# 20-Power-P1V8.net
KiCad netlist of a schematic drawn in Altium Designer
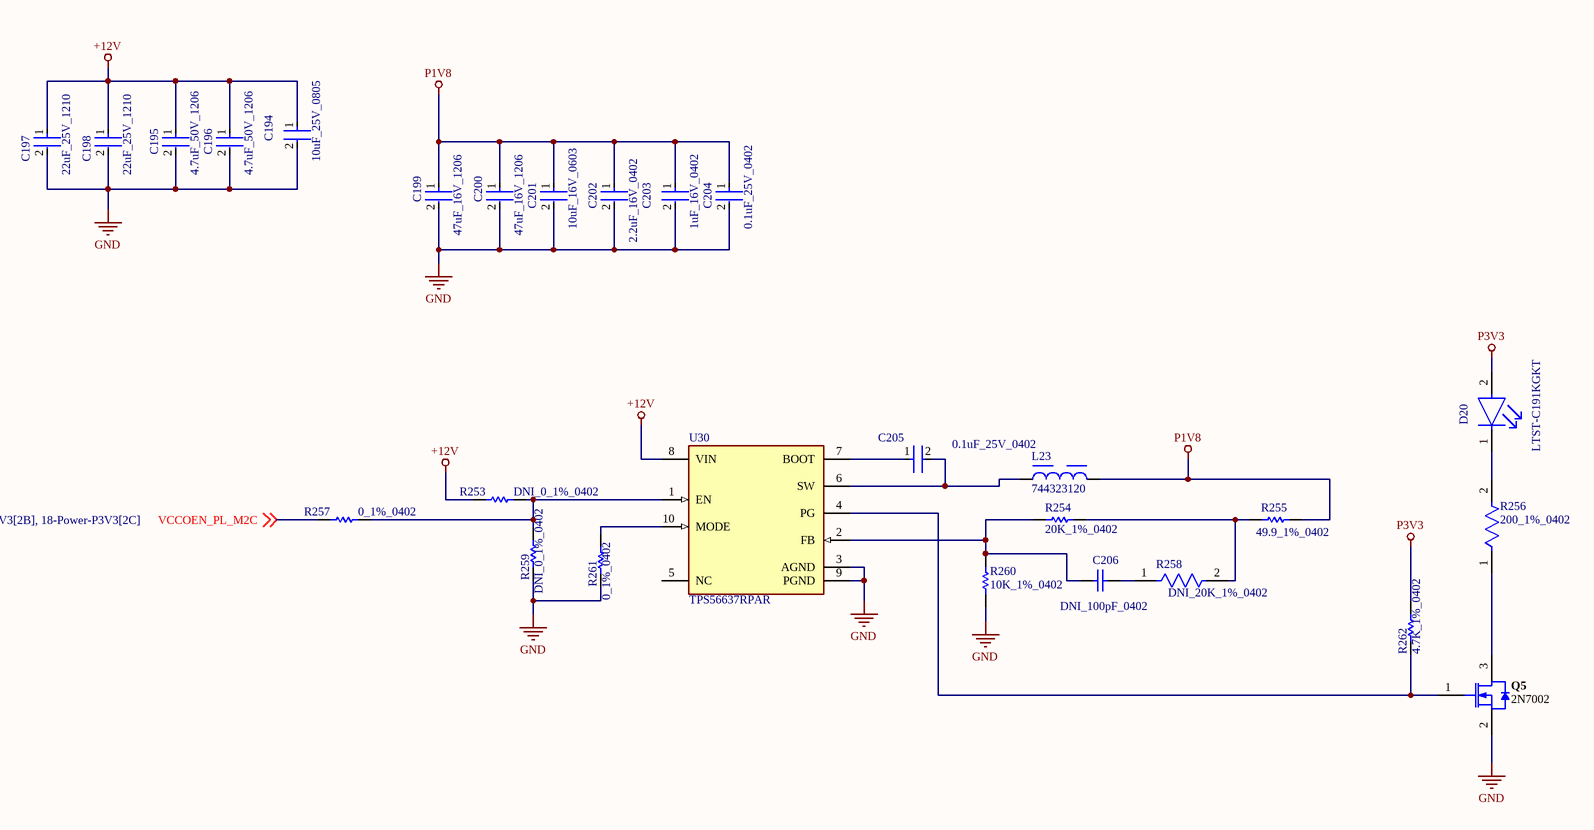
[diagram p0: 20-Power-P1V8.SchDoc]

(export (version "E")
  (design (tool "Eeschema 10.0.6"))
  (components
    (comp (ref "C194")
      (value "10uF_25V_0805")
      (footprint "FP-0805-L_2_0_0_2-W_1_25-MFG")
      (description "Multilayer Ceramic Capacitor 10uF 25V X5R 10% SMD 0805 T/R")
      (fields (field (name "VOLTAGE") "16V") (field (name "TOLERANCE") "10%"))
      (libsource (lib "Altium Content Vault") (part "02cd4be3c70576c341d710602a673aa"))
    )
    (comp (ref "C195")
      (value "4.7uF_50V_1206")
      (footprint "FP-GRM31C-0_2-e0_3_0_8-IPC_C")
      (description "Chip Multilayer Ceramic Capacitors for General Purpose, 1206, 4.7uF, X7R, 15%, 10%, 50V")
      (fields (field (name "VOLTAGE") "50V") (field (name "TOLERANCE") "10%"))
      (libsource (lib "Altium Content Vault") (part "02cd4be3c70576c341d710602a673aa"))
    )
    (comp (ref "C196")
      (value "4.7uF_50V_1206")
      (footprint "FP-GRM31C-0_2-e0_3_0_8-IPC_C")
      (description "Chip Multilayer Ceramic Capacitors for General Purpose, 1206, 4.7uF, X7R, 15%, 10%, 50V")
      (fields (field (name "VOLTAGE") "50V") (field (name "TOLERANCE") "10%"))
      (libsource (lib "Altium Content Vault") (part "02cd4be3c70576c341d710602a673aa"))
    )
    (comp (ref "C197")
      (value "22uF_25V_1210")
      (footprint "FP-MK325M-MFG")
      (description "CAP CER 22UF 25V X5R 1210")
      (fields (field (name "TOLERANCE") "20%"))
      (libsource (lib "Altium Content Vault") (part "b4654b650e69147ec39a6b967a45e02"))
    )
    (comp (ref "C198")
      (value "22uF_25V_1210")
      (footprint "FP-MK325M-MFG")
      (description "CAP CER 22UF 25V X5R 1210")
      (fields (field (name "TOLERANCE") "20%"))
      (libsource (lib "Altium Content Vault") (part "b4654b650e69147ec39a6b967a45e02"))
    )
    (comp (ref "C199")
      (value "47uF_16V_1206")
      (footprint "FP-C3216-160-0_2-MFG")
      (description "Multilayer Ceramic Capacitors 47uF ±20% 16V X5R SMD 1206")
      (fields (field (name "TOLERANCE") "20%"))
      (libsource (lib "Altium Content Vault") (part "11868f565c42a9108669ba33697ecf6"))
    )
    (comp (ref "C200")
      (value "47uF_16V_1206")
      (footprint "FP-C3216-160-0_2-MFG")
      (description "Multilayer Ceramic Capacitors 47uF ±20% 16V X5R SMD 1206")
      (fields (field (name "TOLERANCE") "20%"))
      (libsource (lib "Altium Content Vault") (part "11868f565c42a9108669ba33697ecf6"))
    )
    (comp (ref "C201")
      (value "10uF_16V_0603")
      (footprint "FP-0603-L_1_6_0_2-W_0_8_0-MFG")
      (description "Multilayer Ceramic Capacitor 10uF 16V X5R 20% SMD 0603 T/R")
      (fields (field (name "TOLERANCE") "20%"))
      (libsource (lib "Altium Content Vault") (part "b4654b650e69147ec39a6b967a45e02"))
    )
    (comp (ref "C202")
      (value "2.2uF_16V_0402")
      (footprint "FP-C1005-050-0_05-IPC_A")
      (description "Multilayer Ceramic Capacitors 2.2μF ±10% 16V X5R SMD 0402")
      (fields (field (name "TOLERANCE") "10%"))
      (libsource (lib "Altium Content Vault") (part "b4654b650e69147ec39a6b967a45e02"))
    )
    (comp (ref "C203")
      (value "1uF_16V_0402")
      (footprint "FP-0402-L_1_0_0_05-W_0_5-IPC_A")
      (description "None")
      (fields (field (name "TOLERANCE") "10%"))
      (libsource (lib "Altium Content Vault") (part "b4654b650e69147ec39a6b967a45e02"))
    )
    (comp (ref "C204")
      (value "0.1uF_25V_0402")
      (footprint "FP-0402-L_1_0_1-W_0_5_0_1-IPC_C")
      (description "General Purpose Ceramic Capacitor, 0402, 100nF, 10%, X7R, 15%, 25V")
      (fields (field (name "VOLTAGE") "25V") (field (name "TOLERANCE") "10%"))
      (libsource (lib "Altium Content Vault") (part "b4654b650e69147ec39a6b967a45e02"))
    )
    (comp (ref "C205")
      (value "0.1uF_25V_0402")
      (footprint "FP-0402-L_1_0_1-W_0_5_0_1-IPC_C")
      (description "General Purpose Ceramic Capacitor, 0402, 100nF, 10%, X7R, 15%, 25V")
      (fields (field (name "VOLTAGE") "25V") (field (name "TOLERANCE") "10%"))
      (libsource (lib "Altium Content Vault") (part "b4654b650e69147ec39a6b967a45e02"))
    )
    (comp (ref "C206")
      (value "DNI_100pF_0402")
      (footprint "CAPC1005X55X25ML05T10")
      (fields (field (name "MANUFACTURER") "Murata") (field (name "PART NUMBER") "GRM1555C1H101JA01D"))
      (libsource (lib "Altium Content Vault") (part "CAP"))
    )
    (comp (ref "D20")
      (value "LTST-C191KGKT")
      (footprint "FP-LTST-C191KGKT-MFG")
      (description "LED GREEN CLEAR SMD")
      (libsource (lib "Altium Content Vault") (part "8706943c75ba83719d021d2fdc84c58"))
    )
    (comp (ref "L23")
      (value "744323120")
      (footprint "WE-HCI_1030")
      (fields (field (name "TOLERANCE") "20%"))
      (libsource (lib "Altium Content Vault") (part "Inductor - 3"))
    )
    (comp (ref "Q5")
      (value "2N7002")
      (footprint "INF-PG-SOT23_M")
      (fields (field (name "MANUFACTURER") "Infineon"))
      (libsource (lib "Altium Content Vault") (part "INF-NDMOS-GSD-3"))
    )
    (comp (ref "R253")
      (value "DNI_0_1%_0402")
      (footprint "RESC1005X40X25LL05T05")
      (description "Chip Resistor, 0 Ohm, 0.1 W, -55 to 155 degC, 0402 (1005 Metric), RoHS, Tape and Reel")
      (fields (field (name "MANUFACTURER") "Panasonic") (field (name "TOLERANCE") "5%"))
      (libsource (lib "Altium Content Vault") (part "RES-2"))
    )
    (comp (ref "R254")
      (value "20K_1%_0402")
      (footprint "RESC1005X40X25NL10T10")
      (fields (field (name "PART NUMBER") "MC00625W0402120K") (field (name "MANUFACTURER") "Multicomp"))
      (libsource (lib "Altium Content Vault") (part "RES"))
    )
    (comp (ref "R255")
      (value "49.9_1%_0402")
      (footprint "RESC1005X40X25LL05T10")
      (fields (field (name "MANUFACTURER") "Yageo / Phycomp") (field (name "PART NUMBER") "RC0402FR-0749R9L"))
      (libsource (lib "Altium Content Vault") (part "RES"))
    )
    (comp (ref "R256")
      (value "200_1%_0402")
      (footprint "FP-ERJ2RK-IPC_A")
      (description "RES SMD 200 OHM 1% 1/10W 0402")
      (fields (field (name "TOLERANCE") "1%"))
      (libsource (lib "Altium Content Vault") (part "1029c3af85768c4190bb7ad29bc67b5"))
    )
    (comp (ref "R257")
      (value "0_1%_0402")
      (footprint "RESC1005X40X25LL05T05")
      (description "Chip Resistor, 0 Ohm, 0.1 W, -55 to 155 degC, 0402 (1005 Metric), RoHS, Tape and Reel")
      (fields (field (name "MANUFACTURER") "Panasonic") (field (name "TOLERANCE") "5%"))
      (libsource (lib "Altium Content Vault") (part "RES-2"))
    )
    (comp (ref "R258")
      (value "DNI_20K_1%_0402")
      (footprint "FP-ERJ2RK-MFG")
      (description "RES SMD 20K OHM 1% 1/10W 0402")
      (fields (field (name "TOLERANCE") "1%"))
      (libsource (lib "Altium Content Vault") (part "1029c3af85768c4190bb7ad29bc67b5"))
    )
    (comp (ref "R259")
      (value "DNI_0_1%_0402")
      (footprint "RESC1005X40X25LL05T05")
      (description "Chip Resistor, 0 Ohm, 0.1 W, -55 to 155 degC, 0402 (1005 Metric), RoHS, Tape and Reel")
      (fields (field (name "MANUFACTURER") "Panasonic") (field (name "TOLERANCE") "5%"))
      (libsource (lib "Altium Content Vault") (part "RES-2"))
    )
    (comp (ref "R260")
      (value "10K_1%_0402")
      (footprint "RESC1005X40X25LL05T05")
      (description "Chip Resistor, 10 KOhm, +/- 1%, 0.1 W, -55 to 155 degC, 0402 (1005 Metric), RoHS, Tape and Reel")
      (fields (field (name "TOLERANCE") "1%") (field (name "MANUFACTURER") "Panasonic"))
      (libsource (lib "Altium Content Vault") (part "RES-2"))
    )
    (comp (ref "R261")
      (value "0_1%_0402")
      (footprint "RESC1005X40X25LL05T05")
      (description "Chip Resistor, 0 Ohm, 0.1 W, -55 to 155 degC, 0402 (1005 Metric), RoHS, Tape and Reel")
      (fields (field (name "MANUFACTURER") "Panasonic") (field (name "TOLERANCE") "5%"))
      (libsource (lib "Altium Content Vault") (part "RES-2"))
    )
    (comp (ref "R262")
      (value "4.7K_1%_0402")
      (footprint "RESC1005X40X25NL10T10")
      (fields (field (name "MANUFACTURER") "Bourns") (field (name "PART NUMBER") "CR0402-FX-4701GLF"))
      (libsource (lib "Altium Content Vault") (part "RES"))
    )
    (comp (ref "U30")
      (value "TPS56637RPAR")
      (footprint "FP-RPA0010A-MFG")
      (description "IC POWER MANAGEMENT")
      (fields
        (field (name "OCTOPART") "https://octopart.com/tps56637rpar-texas+instruments-97650653")
        (field (name "MANUFACTURER") "Texas Instruments")
      )
      (libsource (lib "Altium Content Vault") (part "31007e10bcfaaa9b7385bfd54c3e755"))
    )
  )
  (nets
    (net (code "1") (name "+12V") (class "Default")
      (node (ref "C194") (pin "1") (pinfunction "1_1") (pintype "passive"))
      (node (ref "C195") (pin "1") (pinfunction "1_1") (pintype "passive"))
      (node (ref "C196") (pin "1") (pinfunction "1_1") (pintype "passive"))
      (node (ref "C197") (pin "1") (pinfunction "1_1") (pintype "passive"))
      (node (ref "C198") (pin "1") (pinfunction "1_1") (pintype "passive"))
      (node (ref "R253") (pin "1") (pinfunction "1_1") (pintype "passive"))
      (node (ref "U30") (pin "8") (pinfunction "VIN_8") (pintype "power_in"))
    )
    (net (code "2") (name "GND") (class "Default")
      (node (ref "C194") (pin "2") (pinfunction "2_2") (pintype "passive"))
      (node (ref "C195") (pin "2") (pinfunction "2_2") (pintype "passive"))
      (node (ref "C196") (pin "2") (pinfunction "2_2") (pintype "passive"))
      (node (ref "C197") (pin "2") (pinfunction "2_2") (pintype "passive"))
      (node (ref "C198") (pin "2") (pinfunction "2_2") (pintype "passive"))
      (node (ref "C199") (pin "2") (pinfunction "2_2") (pintype "passive"))
      (node (ref "C200") (pin "2") (pinfunction "2_2") (pintype "passive"))
      (node (ref "C201") (pin "2") (pinfunction "2_2") (pintype "passive"))
      (node (ref "C202") (pin "2") (pinfunction "2_2") (pintype "passive"))
      (node (ref "C203") (pin "2") (pinfunction "2_2") (pintype "passive"))
      (node (ref "C204") (pin "2") (pinfunction "2_2") (pintype "passive"))
      (node (ref "Q5") (pin "2") (pinfunction "SOURCE_2") (pintype "passive"))
      (node (ref "R259") (pin "1") (pinfunction "1_1") (pintype "passive"))
      (node (ref "R260") (pin "1") (pinfunction "1_1") (pintype "passive"))
      (node (ref "R261") (pin "1") (pinfunction "1_1") (pintype "passive"))
      (node (ref "U30") (pin "3") (pinfunction "AGND_3") (pintype "power_in"))
      (node (ref "U30") (pin "9") (pinfunction "PGND_9") (pintype "power_in"))
    )
    (net (code "3") (name "Net-(C206-Pad2)") (class "Default")
      (node (ref "C206") (pin "2") (pinfunction "2_2") (pintype "passive"))
      (node (ref "R258") (pin "1") (pinfunction "1_1") (pintype "passive"))
    )
    (net (code "4") (name "Net-(D20-C)") (class "Default")
      (node (ref "D20") (pin "1") (pinfunction "C_1") (pintype "passive"))
      (node (ref "R256") (pin "2") (pinfunction "2_2") (pintype "passive"))
    )
    (net (code "5") (name "Net-(Q5-DRAIN)") (class "Default")
      (node (ref "Q5") (pin "3") (pinfunction "DRAIN_3") (pintype "passive"))
      (node (ref "R256") (pin "1") (pinfunction "1_1") (pintype "passive"))
    )
    (net (code "6") (name "Net-(Q5-GATE)") (class "Default")
      (node (ref "Q5") (pin "1") (pinfunction "GATE_1") (pintype "passive"))
      (node (ref "R262") (pin "1") (pinfunction "1_1") (pintype "passive"))
      (node (ref "U30") (pin "4") (pinfunction "PG_4") (pintype "open_collector"))
    )
    (net (code "7") (name "Net-(R254-Pad2)") (class "Default")
      (node (ref "R254") (pin "2") (pinfunction "2_2") (pintype "passive"))
      (node (ref "R255") (pin "1") (pinfunction "1_1") (pintype "passive"))
      (node (ref "R258") (pin "2") (pinfunction "2_2") (pintype "passive"))
    )
    (net (code "8") (name "Net-(U30-BOOT)") (class "Default")
      (node (ref "C205") (pin "1") (pinfunction "1_1") (pintype "passive"))
      (node (ref "U30") (pin "7") (pinfunction "BOOT_7") (pintype "power_in"))
    )
    (net (code "9") (name "Net-(U30-EN)") (class "Default")
      (node (ref "R253") (pin "2") (pinfunction "2_2") (pintype "passive"))
      (node (ref "R257") (pin "2") (pinfunction "2_2") (pintype "passive"))
      (node (ref "R259") (pin "2") (pinfunction "2_2") (pintype "passive"))
      (node (ref "U30") (pin "1") (pinfunction "EN_1") (pintype "input"))
    )
    (net (code "10") (name "Net-(U30-FB)") (class "Default")
      (node (ref "C206") (pin "1") (pinfunction "1_1") (pintype "passive"))
      (node (ref "R254") (pin "1") (pinfunction "1_1") (pintype "passive"))
      (node (ref "R260") (pin "2") (pinfunction "2_2") (pintype "passive"))
      (node (ref "U30") (pin "2") (pinfunction "FB_2") (pintype "input"))
    )
    (net (code "11") (name "Net-(U30-MODE)") (class "Default")
      (node (ref "R261") (pin "2") (pinfunction "2_2") (pintype "passive"))
      (node (ref "U30") (pin "10") (pinfunction "MODE_10") (pintype "input"))
    )
    (net (code "12") (name "Net-(U30-SW)") (class "Default")
      (node (ref "C205") (pin "2") (pinfunction "2_2") (pintype "passive"))
      (node (ref "L23") (pin "1") (pinfunction "1_1") (pintype "passive"))
      (node (ref "U30") (pin "6") (pinfunction "SW_6") (pintype "power_in"))
    )
    (net (code "13") (name "P1V8") (class "Default")
      (node (ref "C199") (pin "1") (pinfunction "1_1") (pintype "passive"))
      (node (ref "C200") (pin "1") (pinfunction "1_1") (pintype "passive"))
      (node (ref "C201") (pin "1") (pinfunction "1_1") (pintype "passive"))
      (node (ref "C202") (pin "1") (pinfunction "1_1") (pintype "passive"))
      (node (ref "C203") (pin "1") (pinfunction "1_1") (pintype "passive"))
      (node (ref "C204") (pin "1") (pinfunction "1_1") (pintype "passive"))
      (node (ref "L23") (pin "2") (pinfunction "2_2") (pintype "passive"))
      (node (ref "R255") (pin "2") (pinfunction "2_2") (pintype "passive"))
    )
    (net (code "14") (name "P3V3") (class "Default")
      (node (ref "D20") (pin "2") (pinfunction "A_2") (pintype "passive"))
      (node (ref "R262") (pin "2") (pinfunction "2_2") (pintype "passive"))
    )
    (net (code "15") (name "VCCOEN_PL_M2C") (class "Default")
      (node (ref "R257") (pin "1") (pinfunction "1_1") (pintype "passive"))
    )
    (net (code "16") (name "unconnected-(U30-NC-Pad5)") (class "Default")
      (node (ref "U30") (pin "5") (pinfunction "NC_5") (pintype "passive"))
    )
  )
)
